# mainboard-dev.net
KiCad netlist of a schematic drawn in EAGLE
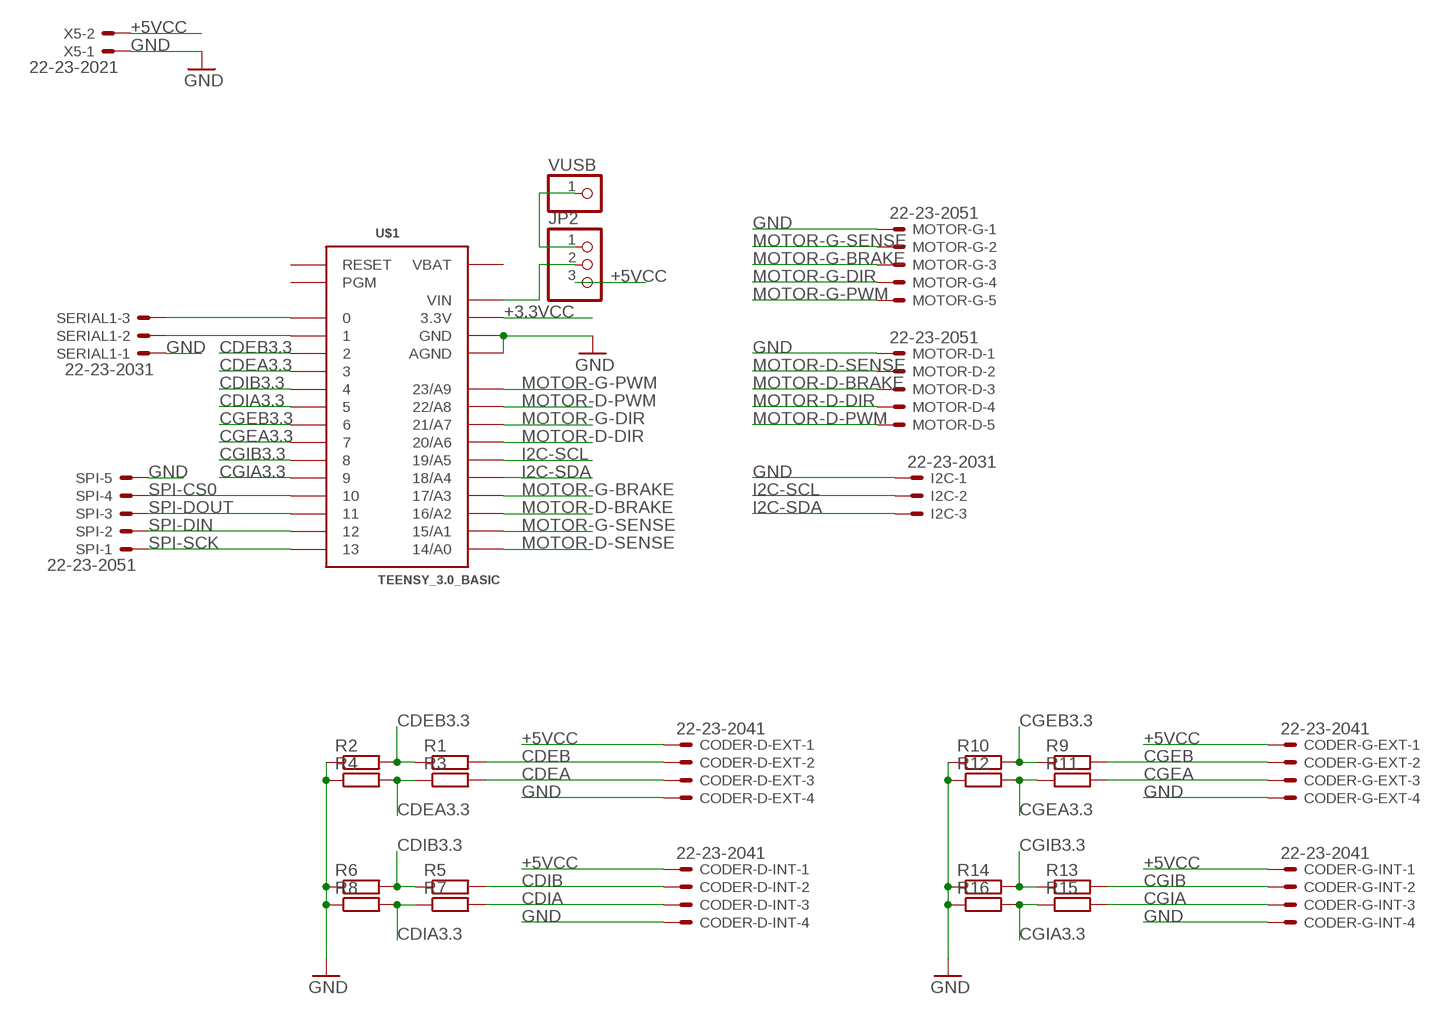
[diagram p0: schematic, sheet 1]

(export (version "E")
  (design (tool "Eeschema 10.0.6"))
  (components
    (comp (ref "CODER-D-EXT")
      (value "22-23-2041")
      (footprint "eagle-import:22-23-2041")
      (fields (field (name "MF") "MOLEX"))
      (libsource (lib "eagle-import") (part "22-23-2041"))
    )
    (comp (ref "CODER-D-INT")
      (value "22-23-2041")
      (footprint "eagle-import:22-23-2041")
      (fields (field (name "MF") "MOLEX"))
      (libsource (lib "eagle-import") (part "22-23-2041"))
    )
    (comp (ref "CODER-G-EXT")
      (value "22-23-2041")
      (footprint "eagle-import:22-23-2041")
      (fields (field (name "MF") "MOLEX"))
      (libsource (lib "eagle-import") (part "22-23-2041"))
    )
    (comp (ref "CODER-G-INT")
      (value "22-23-2041")
      (footprint "eagle-import:22-23-2041")
      (fields (field (name "MF") "MOLEX"))
      (libsource (lib "eagle-import") (part "22-23-2041"))
    )
    (comp (ref "I2C")
      (value "22-23-2031")
      (footprint "eagle-import:22-23-2031")
      (fields (field (name "MF") "MOLEX"))
      (libsource (lib "eagle-import") (part "22-23-2031"))
    )
    (comp (ref "JP2")
      (value "PINHD-1X3")
      (footprint "eagle-import:1X03")
      (libsource (lib "eagle-import") (part "PINHD-1X3"))
    )
    (comp (ref "MOTOR-D")
      (value "22-23-2051")
      (footprint "eagle-import:22-23-2051")
      (fields (field (name "MF") "MOLEX"))
      (libsource (lib "eagle-import") (part "22-23-2051"))
    )
    (comp (ref "MOTOR-G")
      (value "22-23-2051")
      (footprint "eagle-import:22-23-2051")
      (fields (field (name "MF") "MOLEX"))
      (libsource (lib "eagle-import") (part "22-23-2051"))
    )
    (comp (ref "R1")
      (value "R-EU_0207/10")
      (footprint "eagle-import:0207_10")
      (libsource (lib "eagle-import") (part "R-EU_0207/10"))
    )
    (comp (ref "R2")
      (value "R-EU_0207/10")
      (footprint "eagle-import:0207_10")
      (libsource (lib "eagle-import") (part "R-EU_0207/10"))
    )
    (comp (ref "R3")
      (value "R-EU_0207/10")
      (footprint "eagle-import:0207_10")
      (libsource (lib "eagle-import") (part "R-EU_0207/10"))
    )
    (comp (ref "R4")
      (value "R-EU_0207/10")
      (footprint "eagle-import:0207_10")
      (libsource (lib "eagle-import") (part "R-EU_0207/10"))
    )
    (comp (ref "R5")
      (value "R-EU_0207/10")
      (footprint "eagle-import:0207_10")
      (libsource (lib "eagle-import") (part "R-EU_0207/10"))
    )
    (comp (ref "R6")
      (value "R-EU_0207/10")
      (footprint "eagle-import:0207_10")
      (libsource (lib "eagle-import") (part "R-EU_0207/10"))
    )
    (comp (ref "R7")
      (value "R-EU_0207/10")
      (footprint "eagle-import:0207_10")
      (libsource (lib "eagle-import") (part "R-EU_0207/10"))
    )
    (comp (ref "R8")
      (value "R-EU_0207/10")
      (footprint "eagle-import:0207_10")
      (libsource (lib "eagle-import") (part "R-EU_0207/10"))
    )
    (comp (ref "R9")
      (value "R-EU_0207/10")
      (footprint "eagle-import:0207_10")
      (libsource (lib "eagle-import") (part "R-EU_0207/10"))
    )
    (comp (ref "R10")
      (value "R-EU_0207/10")
      (footprint "eagle-import:0207_10")
      (libsource (lib "eagle-import") (part "R-EU_0207/10"))
    )
    (comp (ref "R11")
      (value "R-EU_0207/10")
      (footprint "eagle-import:0207_10")
      (libsource (lib "eagle-import") (part "R-EU_0207/10"))
    )
    (comp (ref "R12")
      (value "R-EU_0207/10")
      (footprint "eagle-import:0207_10")
      (libsource (lib "eagle-import") (part "R-EU_0207/10"))
    )
    (comp (ref "R13")
      (value "R-EU_0207/10")
      (footprint "eagle-import:0207_10")
      (libsource (lib "eagle-import") (part "R-EU_0207/10"))
    )
    (comp (ref "R14")
      (value "R-EU_0207/10")
      (footprint "eagle-import:0207_10")
      (libsource (lib "eagle-import") (part "R-EU_0207/10"))
    )
    (comp (ref "R15")
      (value "R-EU_0207/10")
      (footprint "eagle-import:0207_10")
      (libsource (lib "eagle-import") (part "R-EU_0207/10"))
    )
    (comp (ref "R16")
      (value "R-EU_0207/10")
      (footprint "eagle-import:0207_10")
      (libsource (lib "eagle-import") (part "R-EU_0207/10"))
    )
    (comp (ref "SERIAL1")
      (value "22-23-2031")
      (footprint "eagle-import:22-23-2031")
      (fields (field (name "MF") "MOLEX"))
      (libsource (lib "eagle-import") (part "22-23-2031"))
    )
    (comp (ref "SPI")
      (value "22-23-2051")
      (footprint "eagle-import:22-23-2051")
      (fields (field (name "MF") "MOLEX"))
      (libsource (lib "eagle-import") (part "22-23-2051"))
    )
    (comp (ref "U$1")
      (value "TEENSY_3.0_BASIC")
      (footprint "eagle-import:TEENSY_3.0_BASIC")
      (libsource (lib "eagle-import") (part "TEENSY_3.0_BASIC"))
    )
    (comp (ref "VUSB")
      (value "PINHD-1X1")
      (footprint "eagle-import:1X01")
      (libsource (lib "eagle-import") (part "PINHD-1X1"))
    )
    (comp (ref "X5")
      (value "22-23-2021")
      (footprint "eagle-import:22-23-2021")
      (fields (field (name "MF") "MOLEX"))
      (libsource (lib "eagle-import") (part "22-23-2021"))
    )
  )
  (nets
    (net (code "1") (name "/+3.3VCC") (class "Default")
      (node (ref "U$1") (pin "3.3V") (pinfunction "3.3V_3.3V") (pintype "power_in"))
      (node (ref "U$1") (pin "3.3V1") (pinfunction "3.3V_3.3V1") (pintype "power_in"))
    )
    (net (code "2") (name "/+5VCC") (class "Default")
      (node (ref "CODER-D-EXT") (pin "1") (pinfunction "S_1") (pintype "passive"))
      (node (ref "CODER-D-INT") (pin "1") (pinfunction "S_1") (pintype "passive"))
      (node (ref "CODER-G-EXT") (pin "1") (pinfunction "S_1") (pintype "passive"))
      (node (ref "CODER-G-INT") (pin "1") (pinfunction "S_1") (pintype "passive"))
      (node (ref "JP2") (pin "3") (pinfunction "3_3") (pintype "passive"))
      (node (ref "X5") (pin "2") (pinfunction "S_2") (pintype "passive"))
    )
    (net (code "3") (name "/CDEA") (class "Default")
      (node (ref "CODER-D-EXT") (pin "3") (pinfunction "S_3") (pintype "passive"))
      (node (ref "R3") (pin "2") (pinfunction "2_2") (pintype "passive"))
    )
    (net (code "4") (name "/CDEA3.3") (class "Default")
      (node (ref "R3") (pin "1") (pinfunction "1_1") (pintype "passive"))
      (node (ref "R4") (pin "2") (pinfunction "2_2") (pintype "passive"))
      (node (ref "U$1") (pin "3") (pinfunction "3_3") (pintype "bidirectional"))
    )
    (net (code "5") (name "/CDEB") (class "Default")
      (node (ref "CODER-D-EXT") (pin "2") (pinfunction "S_2") (pintype "passive"))
      (node (ref "R1") (pin "2") (pinfunction "2_2") (pintype "passive"))
    )
    (net (code "6") (name "/CDEB3.3") (class "Default")
      (node (ref "R1") (pin "1") (pinfunction "1_1") (pintype "passive"))
      (node (ref "R2") (pin "2") (pinfunction "2_2") (pintype "passive"))
      (node (ref "U$1") (pin "2") (pinfunction "2_2") (pintype "bidirectional"))
    )
    (net (code "7") (name "/CDIA") (class "Default")
      (node (ref "CODER-D-INT") (pin "3") (pinfunction "S_3") (pintype "passive"))
      (node (ref "R7") (pin "2") (pinfunction "2_2") (pintype "passive"))
    )
    (net (code "8") (name "/CDIA3.3") (class "Default")
      (node (ref "R7") (pin "1") (pinfunction "1_1") (pintype "passive"))
      (node (ref "R8") (pin "2") (pinfunction "2_2") (pintype "passive"))
      (node (ref "U$1") (pin "5") (pinfunction "5_5") (pintype "bidirectional"))
    )
    (net (code "9") (name "/CDIB") (class "Default")
      (node (ref "CODER-D-INT") (pin "2") (pinfunction "S_2") (pintype "passive"))
      (node (ref "R5") (pin "2") (pinfunction "2_2") (pintype "passive"))
    )
    (net (code "10") (name "/CDIB3.3") (class "Default")
      (node (ref "R5") (pin "1") (pinfunction "1_1") (pintype "passive"))
      (node (ref "R6") (pin "2") (pinfunction "2_2") (pintype "passive"))
      (node (ref "U$1") (pin "4") (pinfunction "4_4") (pintype "bidirectional"))
    )
    (net (code "11") (name "/CGEA") (class "Default")
      (node (ref "CODER-G-EXT") (pin "3") (pinfunction "S_3") (pintype "passive"))
      (node (ref "R11") (pin "2") (pinfunction "2_2") (pintype "passive"))
    )
    (net (code "12") (name "/CGEA3.3") (class "Default")
      (node (ref "R11") (pin "1") (pinfunction "1_1") (pintype "passive"))
      (node (ref "R12") (pin "2") (pinfunction "2_2") (pintype "passive"))
      (node (ref "U$1") (pin "7") (pinfunction "7_7") (pintype "bidirectional"))
    )
    (net (code "13") (name "/CGEB") (class "Default")
      (node (ref "CODER-G-EXT") (pin "2") (pinfunction "S_2") (pintype "passive"))
      (node (ref "R9") (pin "2") (pinfunction "2_2") (pintype "passive"))
    )
    (net (code "14") (name "/CGEB3.3") (class "Default")
      (node (ref "R10") (pin "2") (pinfunction "2_2") (pintype "passive"))
      (node (ref "R9") (pin "1") (pinfunction "1_1") (pintype "passive"))
      (node (ref "U$1") (pin "6") (pinfunction "6_6") (pintype "bidirectional"))
    )
    (net (code "15") (name "/CGIA") (class "Default")
      (node (ref "CODER-G-INT") (pin "3") (pinfunction "S_3") (pintype "passive"))
      (node (ref "R15") (pin "2") (pinfunction "2_2") (pintype "passive"))
    )
    (net (code "16") (name "/CGIA3.3") (class "Default")
      (node (ref "R15") (pin "1") (pinfunction "1_1") (pintype "passive"))
      (node (ref "R16") (pin "2") (pinfunction "2_2") (pintype "passive"))
      (node (ref "U$1") (pin "9") (pinfunction "9_9") (pintype "bidirectional"))
    )
    (net (code "17") (name "/CGIB") (class "Default")
      (node (ref "CODER-G-INT") (pin "2") (pinfunction "S_2") (pintype "passive"))
      (node (ref "R13") (pin "2") (pinfunction "2_2") (pintype "passive"))
    )
    (net (code "18") (name "/CGIB3.3") (class "Default")
      (node (ref "R13") (pin "1") (pinfunction "1_1") (pintype "passive"))
      (node (ref "R14") (pin "2") (pinfunction "2_2") (pintype "passive"))
      (node (ref "U$1") (pin "8") (pinfunction "8_8") (pintype "bidirectional"))
    )
    (net (code "19") (name "/I2C-SCL") (class "Default")
      (node (ref "I2C") (pin "2") (pinfunction "S_2") (pintype "passive"))
      (node (ref "U$1") (pin "19/A5") (pinfunction "19/A5_19/A5") (pintype "bidirectional"))
    )
    (net (code "20") (name "/I2C-SDA") (class "Default")
      (node (ref "I2C") (pin "3") (pinfunction "S_3") (pintype "passive"))
      (node (ref "U$1") (pin "18/A4") (pinfunction "18/A4_18/A4") (pintype "bidirectional"))
    )
    (net (code "21") (name "/MOTOR-D-BRAKE") (class "Default")
      (node (ref "MOTOR-D") (pin "3") (pinfunction "S_3") (pintype "passive"))
      (node (ref "U$1") (pin "16/A2") (pinfunction "16/A2_16/A2") (pintype "bidirectional"))
    )
    (net (code "22") (name "/MOTOR-D-DIR") (class "Default")
      (node (ref "MOTOR-D") (pin "4") (pinfunction "S_4") (pintype "passive"))
      (node (ref "U$1") (pin "20/A6") (pinfunction "20/A6_20/A6") (pintype "bidirectional"))
    )
    (net (code "23") (name "/MOTOR-D-PWM") (class "Default")
      (node (ref "MOTOR-D") (pin "5") (pinfunction "S_5") (pintype "passive"))
      (node (ref "U$1") (pin "22/A8") (pinfunction "22/A8_22/A8") (pintype "bidirectional"))
    )
    (net (code "24") (name "/MOTOR-D-SENSE") (class "Default")
      (node (ref "MOTOR-D") (pin "2") (pinfunction "S_2") (pintype "passive"))
      (node (ref "U$1") (pin "14/A0") (pinfunction "14/A0_14/A0") (pintype "bidirectional"))
    )
    (net (code "25") (name "/MOTOR-G-BRAKE") (class "Default")
      (node (ref "MOTOR-G") (pin "3") (pinfunction "S_3") (pintype "passive"))
      (node (ref "U$1") (pin "17/A3") (pinfunction "17/A3_17/A3") (pintype "bidirectional"))
    )
    (net (code "26") (name "/MOTOR-G-DIR") (class "Default")
      (node (ref "MOTOR-G") (pin "4") (pinfunction "S_4") (pintype "passive"))
      (node (ref "U$1") (pin "21/A7") (pinfunction "21/A7_21/A7") (pintype "bidirectional"))
    )
    (net (code "27") (name "/MOTOR-G-PWM") (class "Default")
      (node (ref "MOTOR-G") (pin "5") (pinfunction "S_5") (pintype "passive"))
      (node (ref "U$1") (pin "23/A9") (pinfunction "23/A9_23/A9") (pintype "bidirectional"))
    )
    (net (code "28") (name "/MOTOR-G-SENSE") (class "Default")
      (node (ref "MOTOR-G") (pin "2") (pinfunction "S_2") (pintype "passive"))
      (node (ref "U$1") (pin "15/A1") (pinfunction "15/A1_15/A1") (pintype "bidirectional"))
    )
    (net (code "29") (name "/SPI-CS0") (class "Default")
      (node (ref "SPI") (pin "4") (pinfunction "S_4") (pintype "passive"))
      (node (ref "U$1") (pin "10") (pinfunction "10_10") (pintype "bidirectional"))
    )
    (net (code "30") (name "/SPI-DIN") (class "Default")
      (node (ref "SPI") (pin "2") (pinfunction "S_2") (pintype "passive"))
      (node (ref "U$1") (pin "12") (pinfunction "12_12") (pintype "bidirectional"))
    )
    (net (code "31") (name "/SPI-DOUT") (class "Default")
      (node (ref "SPI") (pin "3") (pinfunction "S_3") (pintype "passive"))
      (node (ref "U$1") (pin "11") (pinfunction "11_11") (pintype "bidirectional"))
    )
    (net (code "32") (name "/SPI-SCK") (class "Default")
      (node (ref "SPI") (pin "1") (pinfunction "S_1") (pintype "passive"))
      (node (ref "U$1") (pin "13") (pinfunction "13_13") (pintype "bidirectional"))
    )
    (net (code "33") (name "/VBAT") (class "Default")
      (node (ref "U$1") (pin "VBAT") (pinfunction "VBAT_VBAT") (pintype "power_in"))
    )
    (net (code "34") (name "GND") (class "Default")
      (node (ref "CODER-D-EXT") (pin "4") (pinfunction "S_4") (pintype "passive"))
      (node (ref "CODER-D-INT") (pin "4") (pinfunction "S_4") (pintype "passive"))
      (node (ref "CODER-G-EXT") (pin "4") (pinfunction "S_4") (pintype "passive"))
      (node (ref "CODER-G-INT") (pin "4") (pinfunction "S_4") (pintype "passive"))
      (node (ref "I2C") (pin "1") (pinfunction "S_1") (pintype "passive"))
      (node (ref "MOTOR-D") (pin "1") (pinfunction "S_1") (pintype "passive"))
      (node (ref "MOTOR-G") (pin "1") (pinfunction "S_1") (pintype "passive"))
      (node (ref "R10") (pin "1") (pinfunction "1_1") (pintype "passive"))
      (node (ref "R12") (pin "1") (pinfunction "1_1") (pintype "passive"))
      (node (ref "R14") (pin "1") (pinfunction "1_1") (pintype "passive"))
      (node (ref "R16") (pin "1") (pinfunction "1_1") (pintype "passive"))
      (node (ref "R2") (pin "1") (pinfunction "1_1") (pintype "passive"))
      (node (ref "R4") (pin "1") (pinfunction "1_1") (pintype "passive"))
      (node (ref "R6") (pin "1") (pinfunction "1_1") (pintype "passive"))
      (node (ref "R8") (pin "1") (pinfunction "1_1") (pintype "passive"))
      (node (ref "SERIAL1") (pin "1") (pinfunction "S_1") (pintype "passive"))
      (node (ref "SPI") (pin "5") (pinfunction "S_5") (pintype "passive"))
      (node (ref "U$1") (pin "AGND") (pinfunction "AGND_AGND") (pintype "power_in"))
      (node (ref "U$1") (pin "GND") (pinfunction "GND_GND") (pintype "power_in"))
      (node (ref "U$1") (pin "GND1") (pinfunction "GND_GND1") (pintype "power_in"))
      (node (ref "X5") (pin "1") (pinfunction "S_1") (pintype "passive"))
    )
    (net (code "35") (name "Net-(JP2-Pad1)") (class "Default")
      (node (ref "JP2") (pin "1") (pinfunction "1_1") (pintype "passive"))
      (node (ref "VUSB") (pin "1") (pinfunction "1_1") (pintype "passive"))
    )
    (net (code "36") (name "Net-(JP2-Pad2)") (class "Default")
      (node (ref "JP2") (pin "2") (pinfunction "2_2") (pintype "passive"))
      (node (ref "U$1") (pin "VIN") (pinfunction "VIN_VIN") (pintype "power_in"))
    )
    (net (code "37") (name "Net-(SERIAL1B-S)") (class "Default")
      (node (ref "SERIAL1") (pin "2") (pinfunction "S_2") (pintype "passive"))
      (node (ref "U$1") (pin "1") (pinfunction "1_1") (pintype "bidirectional"))
    )
    (net (code "38") (name "Net-(SERIAL1C-S)") (class "Default")
      (node (ref "SERIAL1") (pin "3") (pinfunction "S_3") (pintype "passive"))
      (node (ref "U$1") (pin "0") (pinfunction "0_0") (pintype "bidirectional"))
    )
    (net (code "39") (name "unconnected-(U$1-PadPGM)") (class "Default")
      (node (ref "U$1") (pin "PGM") (pinfunction "PGM_PGM") (pintype "bidirectional"))
    )
    (net (code "40") (name "unconnected-(U$1-PadRESET)") (class "Default")
      (node (ref "U$1") (pin "RESET") (pinfunction "RESET_RESET") (pintype "bidirectional"))
    )
  )
)
